# CDH-v4_1.net
KiCad netlist of a schematic drawn in EAGLE
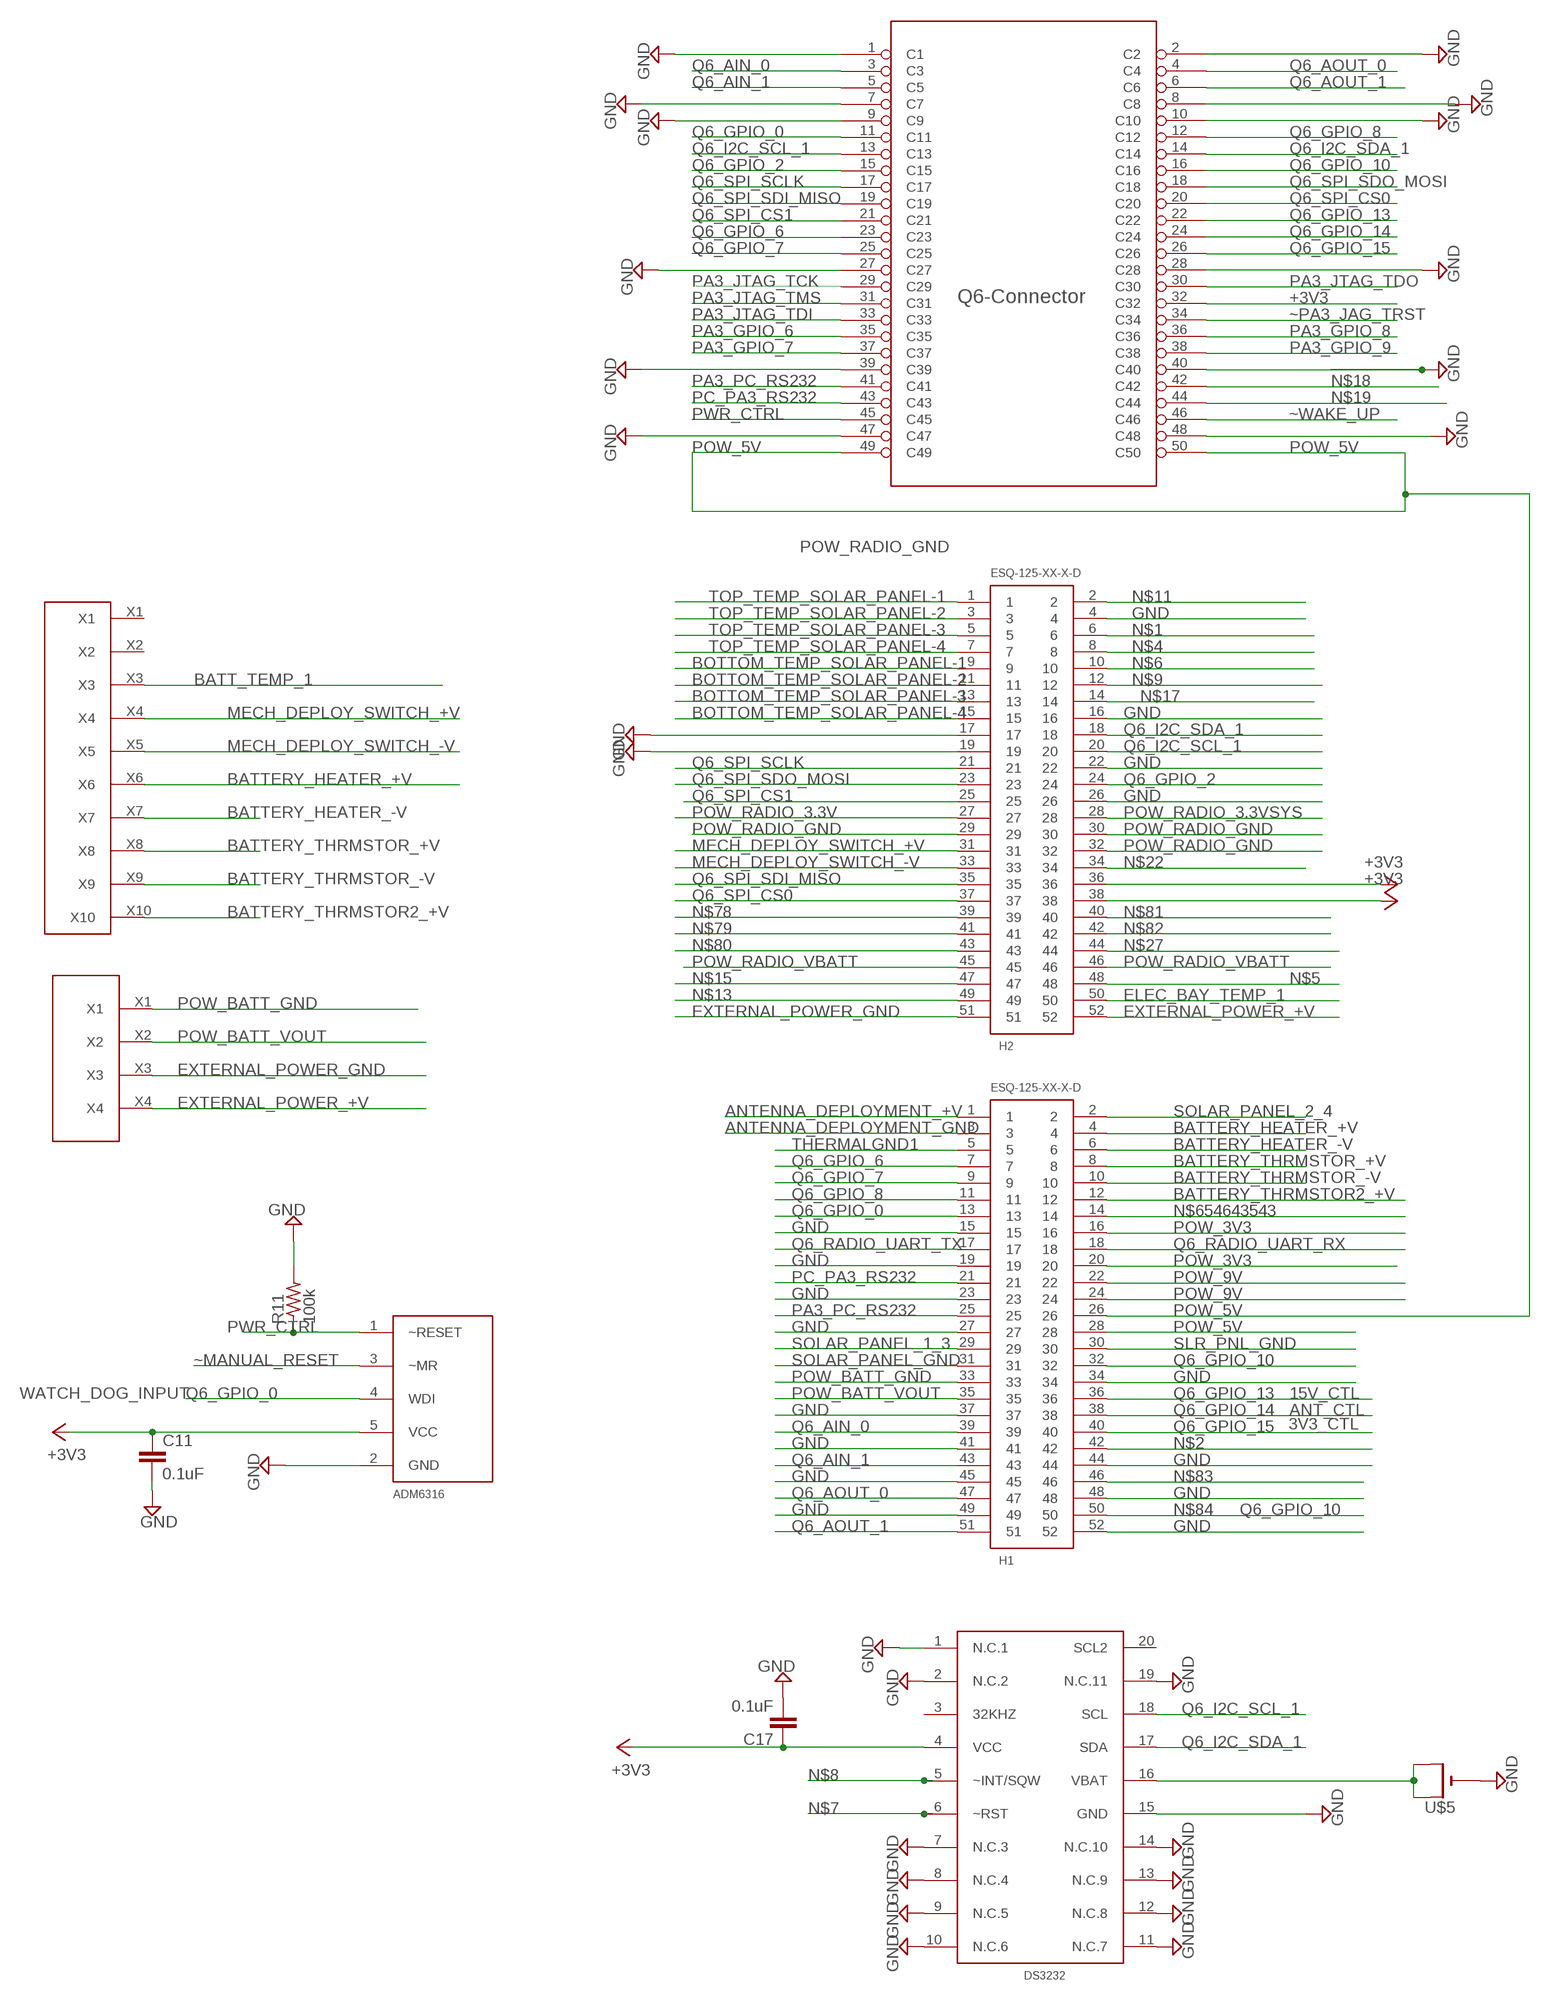
[diagram p0: schematic, sheet 1, part 1 of 2]
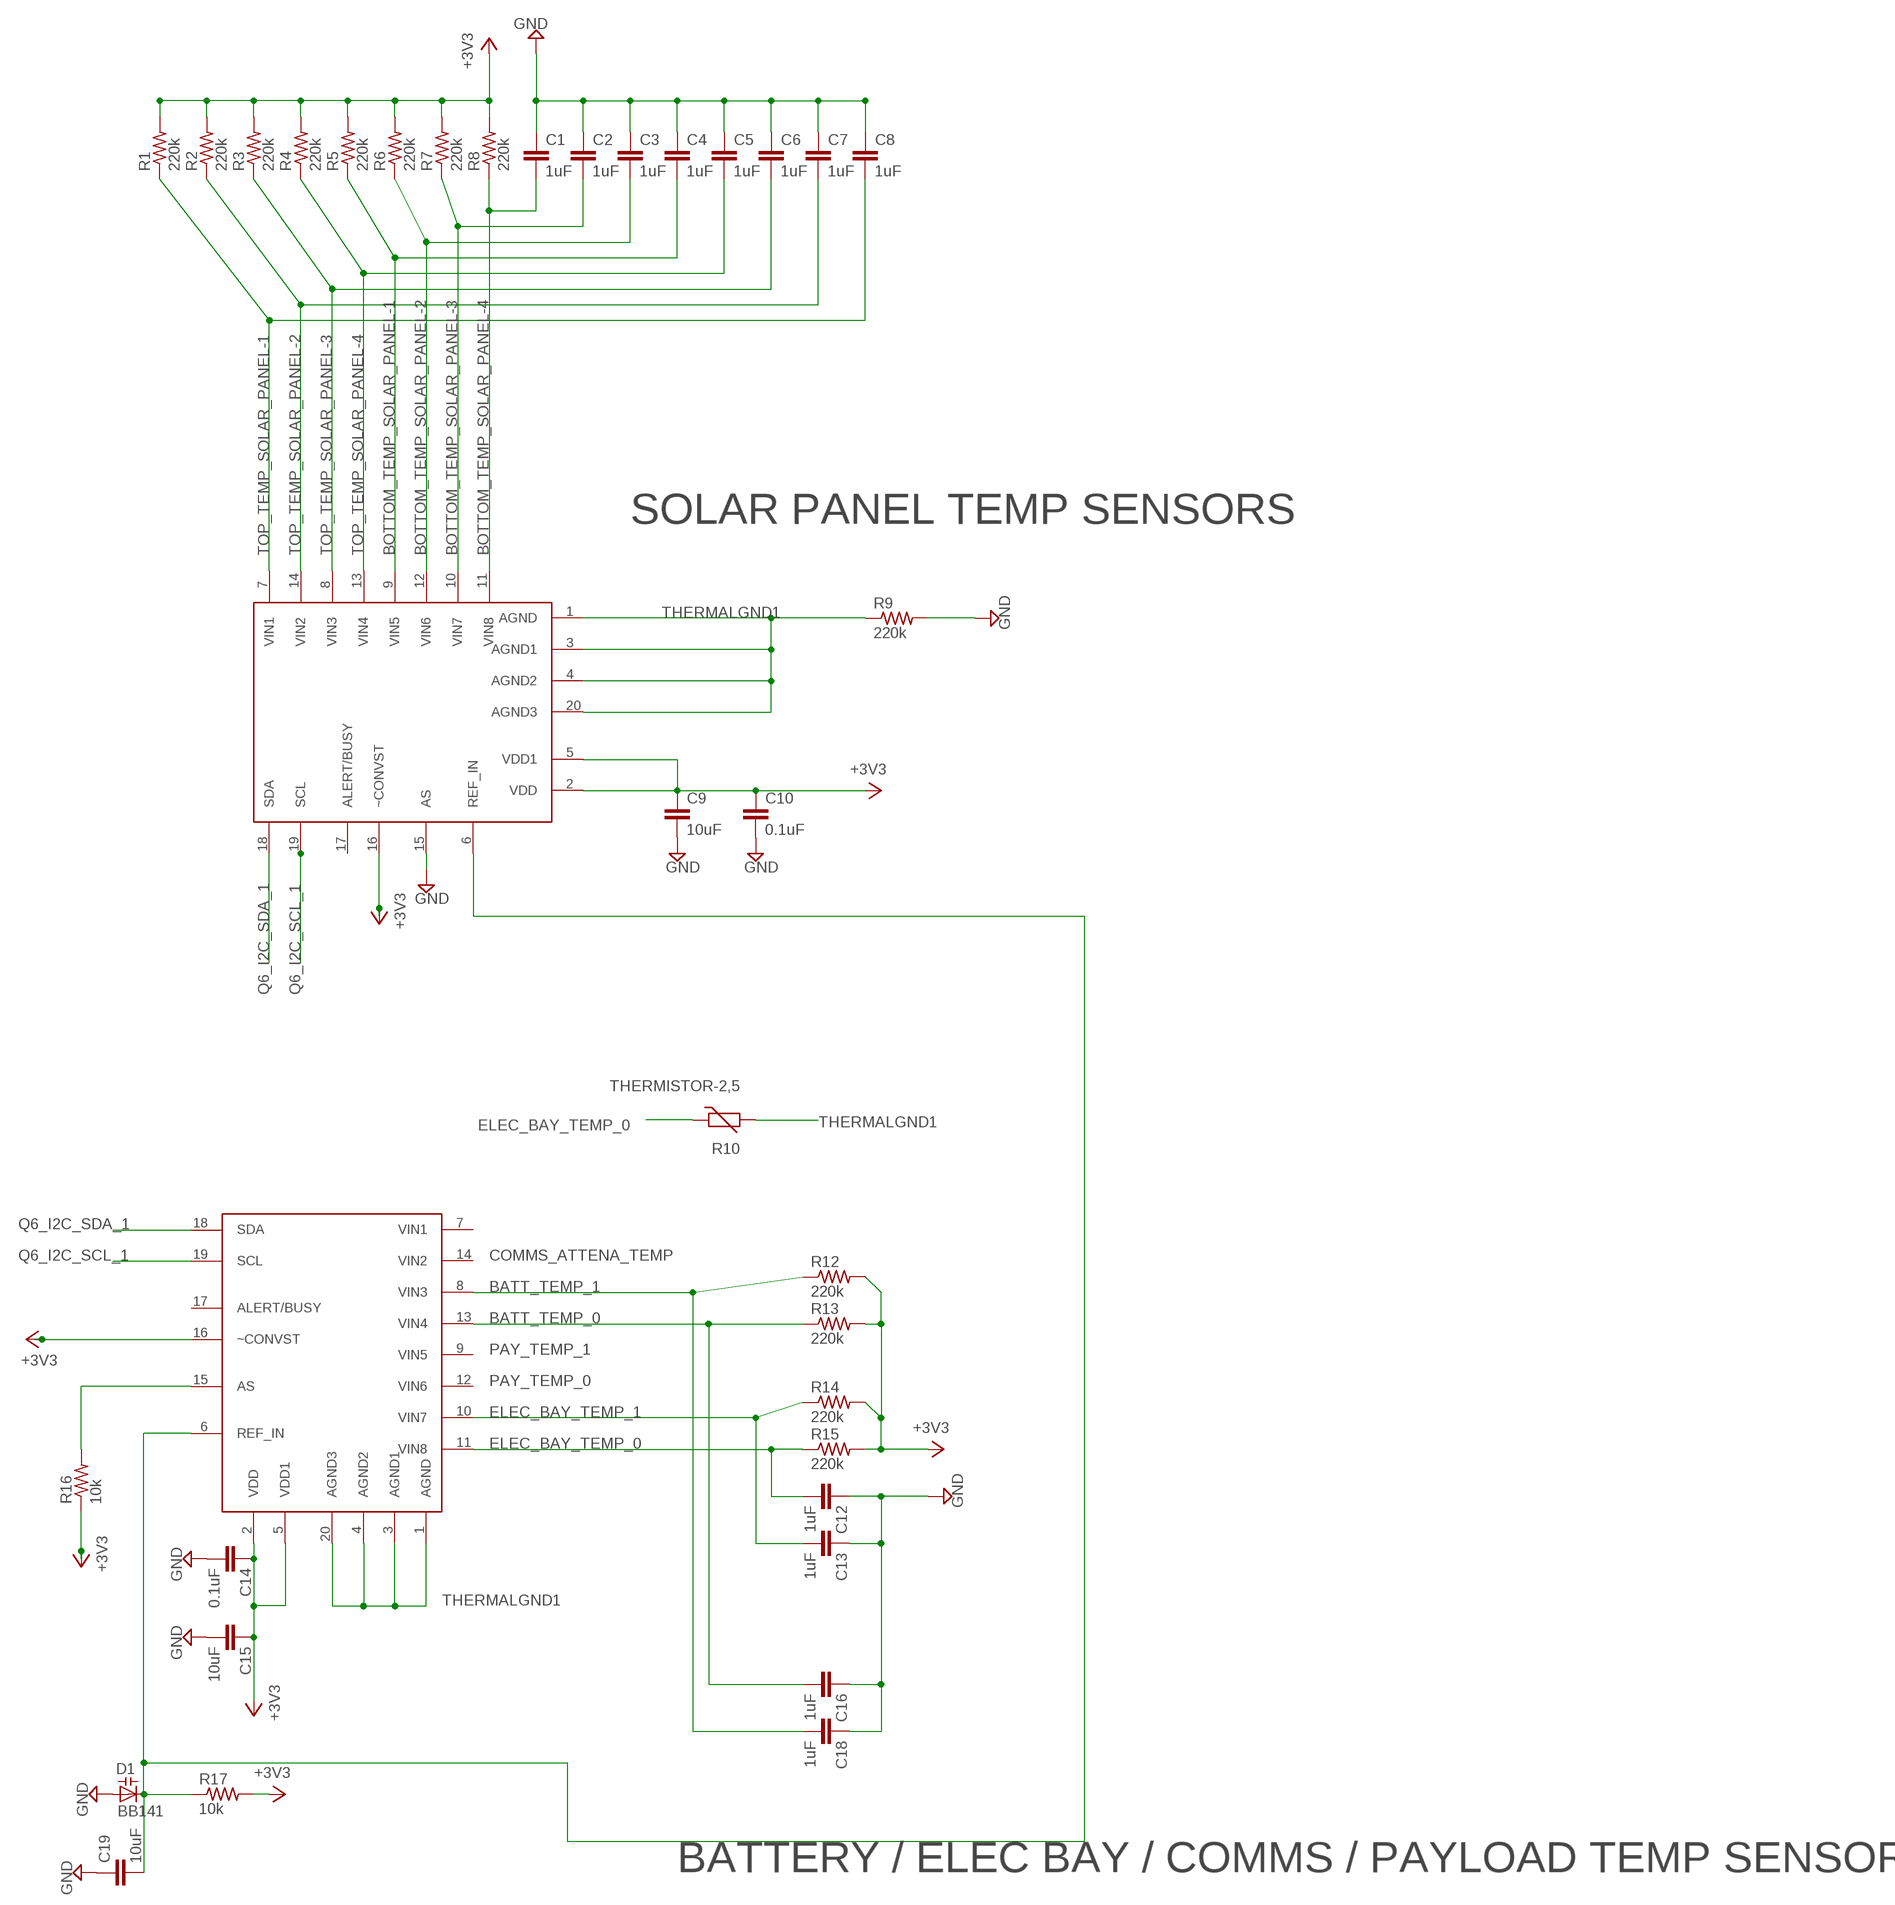
[diagram p1: schematic, sheet 1, part 2 of 2]

(export (version "E")
  (design (tool "Eeschema 10.0.6"))
  (components
    (comp (ref "ADC_TEMP_1")
      (value "AD7998-1")
      (footprint "eagle-import:TSSOP20")
      (libsource (lib "eagle-import") (part "AD7998-1"))
    )
    (comp (ref "ADC_TEMP_2")
      (value "AD7998-1")
      (footprint "eagle-import:TSSOP20")
      (libsource (lib "eagle-import") (part "AD7998-1"))
    )
    (comp (ref "C1")
      (value "1uF")
      (footprint "eagle-import:C2012")
      (libsource (lib "eagle-import") (part "C-EUC2012"))
    )
    (comp (ref "C2")
      (value "1uF")
      (footprint "eagle-import:C2012")
      (libsource (lib "eagle-import") (part "C-EUC2012"))
    )
    (comp (ref "C3")
      (value "1uF")
      (footprint "eagle-import:C2012")
      (libsource (lib "eagle-import") (part "C-EUC2012"))
    )
    (comp (ref "C4")
      (value "1uF")
      (footprint "eagle-import:C2012")
      (libsource (lib "eagle-import") (part "C-EUC2012"))
    )
    (comp (ref "C5")
      (value "1uF")
      (footprint "eagle-import:C2012")
      (libsource (lib "eagle-import") (part "C-EUC2012"))
    )
    (comp (ref "C6")
      (value "1uF")
      (footprint "eagle-import:C2012")
      (libsource (lib "eagle-import") (part "C-EUC2012"))
    )
    (comp (ref "C7")
      (value "1uF")
      (footprint "eagle-import:C2012")
      (libsource (lib "eagle-import") (part "C-EUC2012"))
    )
    (comp (ref "C8")
      (value "1uF")
      (footprint "eagle-import:C2012")
      (libsource (lib "eagle-import") (part "C-EUC2012"))
    )
    (comp (ref "C9")
      (value "10uF")
      (footprint "eagle-import:C2012")
      (libsource (lib "eagle-import") (part "C-EUC2012"))
    )
    (comp (ref "C10")
      (value "0.1uF")
      (footprint "eagle-import:C2012")
      (libsource (lib "eagle-import") (part "C-EUC2012"))
    )
    (comp (ref "C11")
      (value "0.1uF")
      (footprint "eagle-import:C2012")
      (libsource (lib "eagle-import") (part "C-EUC2012"))
    )
    (comp (ref "C12")
      (value "1uF")
      (footprint "eagle-import:C2012")
      (libsource (lib "eagle-import") (part "C-EUC2012"))
    )
    (comp (ref "C13")
      (value "1uF")
      (footprint "eagle-import:C2012")
      (libsource (lib "eagle-import") (part "C-EUC2012"))
    )
    (comp (ref "C14")
      (value "0.1uF")
      (footprint "eagle-import:C2012")
      (libsource (lib "eagle-import") (part "C-EUC2012"))
    )
    (comp (ref "C15")
      (value "10uF")
      (footprint "eagle-import:C2012")
      (libsource (lib "eagle-import") (part "C-EUC2012"))
    )
    (comp (ref "C16")
      (value "1uF")
      (footprint "eagle-import:C2012")
      (libsource (lib "eagle-import") (part "C-EUC2012"))
    )
    (comp (ref "C17")
      (value "0.1uF")
      (footprint "eagle-import:C2012")
      (libsource (lib "eagle-import") (part "C-EUC2012"))
    )
    (comp (ref "C18")
      (value "1uF")
      (footprint "eagle-import:C2012")
      (libsource (lib "eagle-import") (part "C-EUC2012"))
    )
    (comp (ref "C19")
      (value "10uF")
      (footprint "eagle-import:C2012")
      (libsource (lib "eagle-import") (part "C-EUC2012"))
    )
    (comp (ref "D1")
      (value "BB141")
      (footprint "eagle-import:SOD523")
      (libsource (lib "eagle-import") (part "BB141"))
    )
    (comp (ref "H1")
      (value "ESQ-125-XX-X-D")
      (footprint "eagle-import:ESQ-125-XX-X-D")
      (libsource (lib "eagle-import") (part "ESQ-125-XX-X-D"))
    )
    (comp (ref "H2")
      (value "ESQ-125-XX-X-D")
      (footprint "eagle-import:ESQ-125-XX-X-D")
      (libsource (lib "eagle-import") (part "ESQ-125-XX-X-D"))
    )
    (comp (ref "R1")
      (value "220k")
      (footprint "eagle-import:R2012")
      (libsource (lib "eagle-import") (part "R-US_R2012"))
    )
    (comp (ref "R2")
      (value "220k")
      (footprint "eagle-import:R2012")
      (libsource (lib "eagle-import") (part "R-US_R2012"))
    )
    (comp (ref "R3")
      (value "220k")
      (footprint "eagle-import:R2012")
      (libsource (lib "eagle-import") (part "R-US_R2012"))
    )
    (comp (ref "R4")
      (value "220k")
      (footprint "eagle-import:R2012")
      (libsource (lib "eagle-import") (part "R-US_R2012"))
    )
    (comp (ref "R5")
      (value "220k")
      (footprint "eagle-import:R2012")
      (libsource (lib "eagle-import") (part "R-US_R2012"))
    )
    (comp (ref "R6")
      (value "220k")
      (footprint "eagle-import:R2012")
      (libsource (lib "eagle-import") (part "R-US_R2012"))
    )
    (comp (ref "R7")
      (value "220k")
      (footprint "eagle-import:R2012")
      (libsource (lib "eagle-import") (part "R-US_R2012"))
    )
    (comp (ref "R8")
      (value "220k")
      (footprint "eagle-import:R2012")
      (libsource (lib "eagle-import") (part "R-US_R2012"))
    )
    (comp (ref "R9")
      (value "220k")
      (footprint "eagle-import:R2012")
      (libsource (lib "eagle-import") (part "R-US_R2012"))
    )
    (comp (ref "R10")
      (value "THERMISTOR-2,5")
      (footprint "eagle-import:RS-2,5")
      (libsource (lib "eagle-import") (part "THERMISTOR-2,5"))
    )
    (comp (ref "R11")
      (value "100k")
      (footprint "eagle-import:R2012")
      (libsource (lib "eagle-import") (part "R-US_R2012"))
    )
    (comp (ref "R12")
      (value "220k")
      (footprint "eagle-import:R2012")
      (libsource (lib "eagle-import") (part "R-US_R2012"))
    )
    (comp (ref "R13")
      (value "220k")
      (footprint "eagle-import:R2012")
      (libsource (lib "eagle-import") (part "R-US_R2012"))
    )
    (comp (ref "R14")
      (value "220k")
      (footprint "eagle-import:R2012")
      (libsource (lib "eagle-import") (part "R-US_R2012"))
    )
    (comp (ref "R15")
      (value "220k")
      (footprint "eagle-import:R2012")
      (libsource (lib "eagle-import") (part "R-US_R2012"))
    )
    (comp (ref "R16")
      (value "10k")
      (footprint "eagle-import:R2012")
      (libsource (lib "eagle-import") (part "R-US_R2012"))
    )
    (comp (ref "R17")
      (value "10k")
      (footprint "eagle-import:R2012")
      (libsource (lib "eagle-import") (part "R-US_R2012"))
    )
    (comp (ref "U$1")
      (value "SMFC")
      (footprint "eagle-import:SFMC-107-01-XX-D")
      (libsource (lib "eagle-import") (part "SMFC"))
    )
    (comp (ref "U$2")
      (value "M80-5000000M1-10-331-000")
      (footprint "eagle-import:M80-5000000M1")
      (libsource (lib "eagle-import") (part "M80-5000000M1-10-331-000"))
    )
    (comp (ref "U$3")
      (value "M80-5000000M1-10-331-00-000")
      (footprint "eagle-import:M80-5000000M1-04-331-00-000")
      (libsource (lib "eagle-import") (part "M80-5000000M1-10-331-00-000"))
    )
    (comp (ref "U$4")
      (value "ADM6316/ADM6320")
      (footprint "eagle-import:SOT23-5")
      (libsource (lib "eagle-import") (part "ADM6316/ADM6320"))
    )
    (comp (ref "U$5")
      (value "CR1220SMT")
      (footprint "eagle-import:CR1220-SMD")
      (libsource (lib "eagle-import") (part "CR1220SMT"))
    )
    (comp (ref "U$6")
      (value "DS3232")
      (footprint "eagle-import:SO20L")
      (libsource (lib "eagle-import") (part "DS3232"))
    )
  )
  (nets
    (net (code "1") (name "+3V3") (class "Default")
      (node (ref "ADC_TEMP_1") (pin "16") (pinfunction "~{CONVST}_16") (pintype "bidirectional"))
      (node (ref "ADC_TEMP_1") (pin "2") (pinfunction "VDD_2") (pintype "bidirectional"))
      (node (ref "ADC_TEMP_1") (pin "5") (pinfunction "VDD1_5") (pintype "bidirectional"))
      (node (ref "ADC_TEMP_2") (pin "16") (pinfunction "~{CONVST}_16") (pintype "bidirectional"))
      (node (ref "ADC_TEMP_2") (pin "2") (pinfunction "VDD_2") (pintype "bidirectional"))
      (node (ref "ADC_TEMP_2") (pin "5") (pinfunction "VDD1_5") (pintype "bidirectional"))
      (node (ref "C10") (pin "1") (pinfunction "1_1") (pintype "passive"))
      (node (ref "C11") (pin "1") (pinfunction "1_1") (pintype "passive"))
      (node (ref "C14") (pin "1") (pinfunction "1_1") (pintype "passive"))
      (node (ref "C15") (pin "1") (pinfunction "1_1") (pintype "passive"))
      (node (ref "C17") (pin "1") (pinfunction "1_1") (pintype "passive"))
      (node (ref "C9") (pin "1") (pinfunction "1_1") (pintype "passive"))
      (node (ref "H2") (pin "36") (pinfunction "36_36") (pintype "bidirectional"))
      (node (ref "H2") (pin "38") (pinfunction "38_38") (pintype "bidirectional"))
      (node (ref "R1") (pin "2") (pinfunction "2_2") (pintype "passive"))
      (node (ref "R12") (pin "2") (pinfunction "2_2") (pintype "passive"))
      (node (ref "R13") (pin "2") (pinfunction "2_2") (pintype "passive"))
      (node (ref "R14") (pin "2") (pinfunction "2_2") (pintype "passive"))
      (node (ref "R15") (pin "2") (pinfunction "2_2") (pintype "passive"))
      (node (ref "R16") (pin "1") (pinfunction "1_1") (pintype "passive"))
      (node (ref "R17") (pin "2") (pinfunction "2_2") (pintype "passive"))
      (node (ref "R2") (pin "2") (pinfunction "2_2") (pintype "passive"))
      (node (ref "R3") (pin "2") (pinfunction "2_2") (pintype "passive"))
      (node (ref "R4") (pin "2") (pinfunction "2_2") (pintype "passive"))
      (node (ref "R5") (pin "2") (pinfunction "2_2") (pintype "passive"))
      (node (ref "R6") (pin "2") (pinfunction "2_2") (pintype "passive"))
      (node (ref "R7") (pin "2") (pinfunction "2_2") (pintype "passive"))
      (node (ref "R8") (pin "2") (pinfunction "2_2") (pintype "passive"))
      (node (ref "U$1") (pin "32") (pinfunction "C32_32") (pintype "bidirectional"))
      (node (ref "U$4") (pin "5") (pinfunction "VCC_5") (pintype "bidirectional"))
      (node (ref "U$6") (pin "4") (pinfunction "VCC_4") (pintype "bidirectional"))
    )
    (net (code "2") (name "/ANTENNA_DEPLOYMENT_+V") (class "Default")
      (node (ref "H1") (pin "1") (pinfunction "1_1") (pintype "bidirectional"))
    )
    (net (code "3") (name "/ANTENNA_DEPLOYMENT_GND") (class "Default")
      (node (ref "H1") (pin "3") (pinfunction "3_3") (pintype "bidirectional"))
    )
    (net (code "4") (name "/BATTERY_HEATER_+V") (class "Default")
      (node (ref "H1") (pin "4") (pinfunction "4_4") (pintype "bidirectional"))
      (node (ref "U$2") (pin "X6") (pinfunction "X6_X6") (pintype "bidirectional"))
    )
    (net (code "5") (name "/BATTERY_HEATER_-V") (class "Default")
      (node (ref "H1") (pin "6") (pinfunction "6_6") (pintype "bidirectional"))
      (node (ref "U$2") (pin "X7") (pinfunction "X7_X7") (pintype "bidirectional"))
    )
    (net (code "6") (name "/BATTERY_THRMSTOR2_+V") (class "Default")
      (node (ref "H1") (pin "12") (pinfunction "12_12") (pintype "bidirectional"))
      (node (ref "U$2") (pin "X10") (pinfunction "X10_X10") (pintype "bidirectional"))
    )
    (net (code "7") (name "/BATTERY_THRMSTOR_+V") (class "Default")
      (node (ref "H1") (pin "8") (pinfunction "8_8") (pintype "bidirectional"))
      (node (ref "U$2") (pin "X8") (pinfunction "X8_X8") (pintype "bidirectional"))
    )
    (net (code "8") (name "/BATTERY_THRMSTOR_-V") (class "Default")
      (node (ref "H1") (pin "10") (pinfunction "10_10") (pintype "bidirectional"))
      (node (ref "U$2") (pin "X9") (pinfunction "X9_X9") (pintype "bidirectional"))
    )
    (net (code "9") (name "/BATT_TEMP_1") (class "Default")
      (node (ref "ADC_TEMP_2") (pin "8") (pinfunction "VIN3_8") (pintype "bidirectional"))
      (node (ref "C18") (pin "2") (pinfunction "2_2") (pintype "passive"))
      (node (ref "R12") (pin "1") (pinfunction "1_1") (pintype "passive"))
      (node (ref "U$2") (pin "X3") (pinfunction "X3_X3") (pintype "bidirectional"))
    )
    (net (code "10") (name "/BOTTOM_TEMP_SOLAR_PANEL-1") (class "Default")
      (node (ref "ADC_TEMP_1") (pin "9") (pinfunction "VIN5_9") (pintype "bidirectional"))
      (node (ref "C4") (pin "2") (pinfunction "2_2") (pintype "passive"))
      (node (ref "H2") (pin "9") (pinfunction "9_9") (pintype "bidirectional"))
      (node (ref "R5") (pin "1") (pinfunction "1_1") (pintype "passive"))
    )
    (net (code "11") (name "/BOTTOM_TEMP_SOLAR_PANEL-2") (class "Default")
      (node (ref "ADC_TEMP_1") (pin "12") (pinfunction "VIN6_12") (pintype "bidirectional"))
      (node (ref "C3") (pin "2") (pinfunction "2_2") (pintype "passive"))
      (node (ref "H2") (pin "11") (pinfunction "11_11") (pintype "bidirectional"))
      (node (ref "R6") (pin "1") (pinfunction "1_1") (pintype "passive"))
    )
    (net (code "12") (name "/BOTTOM_TEMP_SOLAR_PANEL-3") (class "Default")
      (node (ref "ADC_TEMP_1") (pin "10") (pinfunction "VIN7_10") (pintype "bidirectional"))
      (node (ref "C2") (pin "2") (pinfunction "2_2") (pintype "passive"))
      (node (ref "H2") (pin "13") (pinfunction "13_13") (pintype "bidirectional"))
      (node (ref "R7") (pin "1") (pinfunction "1_1") (pintype "passive"))
    )
    (net (code "13") (name "/BOTTOM_TEMP_SOLAR_PANEL-4") (class "Default")
      (node (ref "ADC_TEMP_1") (pin "11") (pinfunction "VIN8_11") (pintype "bidirectional"))
      (node (ref "C1") (pin "2") (pinfunction "2_2") (pintype "passive"))
      (node (ref "H2") (pin "15") (pinfunction "15_15") (pintype "bidirectional"))
      (node (ref "R8") (pin "1") (pinfunction "1_1") (pintype "passive"))
    )
    (net (code "14") (name "/ELEC_BAY_TEMP_0") (class "Default")
      (node (ref "ADC_TEMP_2") (pin "11") (pinfunction "VIN8_11") (pintype "bidirectional"))
      (node (ref "C12") (pin "2") (pinfunction "2_2") (pintype "passive"))
      (node (ref "R10") (pin "1") (pinfunction "1_1") (pintype "passive"))
      (node (ref "R15") (pin "1") (pinfunction "1_1") (pintype "passive"))
    )
    (net (code "15") (name "/ELEC_BAY_TEMP_1") (class "Default")
      (node (ref "ADC_TEMP_2") (pin "10") (pinfunction "VIN7_10") (pintype "bidirectional"))
      (node (ref "C13") (pin "2") (pinfunction "2_2") (pintype "passive"))
      (node (ref "H2") (pin "50") (pinfunction "50_50") (pintype "bidirectional"))
      (node (ref "R14") (pin "1") (pinfunction "1_1") (pintype "passive"))
    )
    (net (code "16") (name "/EXTERNAL_POWER_+V") (class "Default")
      (node (ref "H2") (pin "52") (pinfunction "52_52") (pintype "bidirectional"))
      (node (ref "U$3") (pin "X4") (pinfunction "X4_X4") (pintype "bidirectional"))
    )
    (net (code "17") (name "/EXTERNAL_POWER_GND") (class "Default")
      (node (ref "H2") (pin "51") (pinfunction "51_51") (pintype "bidirectional"))
      (node (ref "U$3") (pin "X3") (pinfunction "X3_X3") (pintype "bidirectional"))
    )
    (net (code "18") (name "/MECH_DEPLOY_SWITCH_+V") (class "Default")
      (node (ref "H2") (pin "31") (pinfunction "31_31") (pintype "bidirectional"))
      (node (ref "U$2") (pin "X4") (pinfunction "X4_X4") (pintype "bidirectional"))
    )
    (net (code "19") (name "/MECH_DEPLOY_SWITCH_-V") (class "Default")
      (node (ref "H2") (pin "33") (pinfunction "33_33") (pintype "bidirectional"))
      (node (ref "U$2") (pin "X5") (pinfunction "X5_X5") (pintype "bidirectional"))
    )
    (net (code "20") (name "/N$1") (class "Default")
      (node (ref "H2") (pin "6") (pinfunction "6_6") (pintype "bidirectional"))
    )
    (net (code "21") (name "/N$2") (class "Default")
      (node (ref "H1") (pin "42") (pinfunction "42_42") (pintype "bidirectional"))
    )
    (net (code "22") (name "/N$4") (class "Default")
      (node (ref "H2") (pin "8") (pinfunction "8_8") (pintype "bidirectional"))
    )
    (net (code "23") (name "/N$5") (class "Default")
      (node (ref "H2") (pin "48") (pinfunction "48_48") (pintype "bidirectional"))
    )
    (net (code "24") (name "/N$6") (class "Default")
      (node (ref "H2") (pin "10") (pinfunction "10_10") (pintype "bidirectional"))
    )
    (net (code "25") (name "/N$7") (class "Default")
      (node (ref "U$6") (pin "6") (pinfunction "~{RST}_6") (pintype "bidirectional"))
    )
    (net (code "26") (name "/N$8") (class "Default")
      (node (ref "U$6") (pin "5") (pinfunction "~{INT/SQW}_5") (pintype "bidirectional"))
    )
    (net (code "27") (name "/N$9") (class "Default")
      (node (ref "H2") (pin "12") (pinfunction "12_12") (pintype "bidirectional"))
    )
    (net (code "28") (name "/N$11") (class "Default")
      (node (ref "H2") (pin "2") (pinfunction "2_2") (pintype "bidirectional"))
    )
    (net (code "29") (name "/N$13") (class "Default")
      (node (ref "H2") (pin "49") (pinfunction "49_49") (pintype "bidirectional"))
    )
    (net (code "30") (name "/N$15") (class "Default")
      (node (ref "H2") (pin "47") (pinfunction "47_47") (pintype "bidirectional"))
    )
    (net (code "31") (name "/N$17") (class "Default")
      (node (ref "H2") (pin "14") (pinfunction "14_14") (pintype "bidirectional"))
    )
    (net (code "32") (name "/N$18") (class "Default")
      (node (ref "U$1") (pin "42") (pinfunction "C42_42") (pintype "bidirectional"))
    )
    (net (code "33") (name "/N$19") (class "Default")
      (node (ref "U$1") (pin "44") (pinfunction "C44_44") (pintype "bidirectional"))
    )
    (net (code "34") (name "/N$22") (class "Default")
      (node (ref "H2") (pin "34") (pinfunction "34_34") (pintype "bidirectional"))
    )
    (net (code "35") (name "/N$27") (class "Default")
      (node (ref "H2") (pin "44") (pinfunction "44_44") (pintype "bidirectional"))
    )
    (net (code "36") (name "/N$78") (class "Default")
      (node (ref "H2") (pin "39") (pinfunction "39_39") (pintype "bidirectional"))
    )
    (net (code "37") (name "/N$79") (class "Default")
      (node (ref "H2") (pin "41") (pinfunction "41_41") (pintype "bidirectional"))
    )
    (net (code "38") (name "/N$80") (class "Default")
      (node (ref "H2") (pin "43") (pinfunction "43_43") (pintype "bidirectional"))
    )
    (net (code "39") (name "/N$81") (class "Default")
      (node (ref "H2") (pin "40") (pinfunction "40_40") (pintype "bidirectional"))
    )
    (net (code "40") (name "/N$82") (class "Default")
      (node (ref "H2") (pin "42") (pinfunction "42_42") (pintype "bidirectional"))
    )
    (net (code "41") (name "/N$83") (class "Default")
      (node (ref "H1") (pin "46") (pinfunction "46_46") (pintype "bidirectional"))
    )
    (net (code "42") (name "/N$84") (class "Default")
      (node (ref "H1") (pin "50") (pinfunction "50_50") (pintype "bidirectional"))
    )
    (net (code "43") (name "/N$654643543") (class "Default")
      (node (ref "H1") (pin "14") (pinfunction "14_14") (pintype "bidirectional"))
    )
    (net (code "44") (name "/PA3_GPIO_6") (class "Default")
      (node (ref "U$1") (pin "35") (pinfunction "C35_35") (pintype "bidirectional"))
    )
    (net (code "45") (name "/PA3_GPIO_7") (class "Default")
      (node (ref "U$1") (pin "37") (pinfunction "C37_37") (pintype "bidirectional"))
    )
    (net (code "46") (name "/PA3_GPIO_8") (class "Default")
      (node (ref "U$1") (pin "36") (pinfunction "C36_36") (pintype "bidirectional"))
    )
    (net (code "47") (name "/PA3_GPIO_9") (class "Default")
      (node (ref "U$1") (pin "38") (pinfunction "C38_38") (pintype "bidirectional"))
    )
    (net (code "48") (name "/PA3_JTAG_TCK") (class "Default")
      (node (ref "U$1") (pin "29") (pinfunction "C29_29") (pintype "bidirectional"))
    )
    (net (code "49") (name "/PA3_JTAG_TDI") (class "Default")
      (node (ref "U$1") (pin "33") (pinfunction "C33_33") (pintype "bidirectional"))
    )
    (net (code "50") (name "/PA3_JTAG_TDO") (class "Default")
      (node (ref "U$1") (pin "30") (pinfunction "C30_30") (pintype "bidirectional"))
    )
    (net (code "51") (name "/PA3_JTAG_TMS") (class "Default")
      (node (ref "U$1") (pin "31") (pinfunction "C31_31") (pintype "bidirectional"))
    )
    (net (code "52") (name "/PA3_PC_RS232") (class "Default")
      (node (ref "H1") (pin "25") (pinfunction "25_25") (pintype "bidirectional"))
      (node (ref "U$1") (pin "41") (pinfunction "C41_41") (pintype "bidirectional"))
    )
    (net (code "53") (name "/PC_PA3_RS232") (class "Default")
      (node (ref "H1") (pin "21") (pinfunction "21_21") (pintype "bidirectional"))
      (node (ref "U$1") (pin "43") (pinfunction "C43_43") (pintype "bidirectional"))
    )
    (net (code "54") (name "/POW_3V3") (class "Default")
      (node (ref "H1") (pin "16") (pinfunction "16_16") (pintype "bidirectional"))
      (node (ref "H1") (pin "20") (pinfunction "20_20") (pintype "bidirectional"))
    )
    (net (code "55") (name "/POW_5V") (class "Default")
      (node (ref "H1") (pin "26") (pinfunction "26_26") (pintype "bidirectional"))
      (node (ref "H1") (pin "28") (pinfunction "28_28") (pintype "bidirectional"))
      (node (ref "U$1") (pin "49") (pinfunction "C49_49") (pintype "bidirectional"))
      (node (ref "U$1") (pin "50") (pinfunction "C50_50") (pintype "bidirectional"))
    )
    (net (code "56") (name "/POW_9V") (class "Default")
      (node (ref "H1") (pin "22") (pinfunction "22_22") (pintype "bidirectional"))
      (node (ref "H1") (pin "24") (pinfunction "24_24") (pintype "bidirectional"))
    )
    (net (code "57") (name "/POW_BATT_GND") (class "Default")
      (node (ref "H1") (pin "33") (pinfunction "33_33") (pintype "bidirectional"))
      (node (ref "U$3") (pin "X1") (pinfunction "X1_X1") (pintype "bidirectional"))
    )
    (net (code "58") (name "/POW_BATT_VOUT") (class "Default")
      (node (ref "H1") (pin "35") (pinfunction "35_35") (pintype "bidirectional"))
      (node (ref "U$3") (pin "X2") (pinfunction "X2_X2") (pintype "bidirectional"))
    )
    (net (code "59") (name "/POW_RADIO_3.3V") (class "Default")
      (node (ref "H2") (pin "27") (pinfunction "27_27") (pintype "bidirectional"))
    )
    (net (code "60") (name "/POW_RADIO_3.3VSYS") (class "Default")
      (node (ref "H2") (pin "28") (pinfunction "28_28") (pintype "bidirectional"))
    )
    (net (code "61") (name "/POW_RADIO_GND") (class "Default")
      (node (ref "H2") (pin "29") (pinfunction "29_29") (pintype "bidirectional"))
      (node (ref "H2") (pin "30") (pinfunction "30_30") (pintype "bidirectional"))
      (node (ref "H2") (pin "32") (pinfunction "32_32") (pintype "bidirectional"))
    )
    (net (code "62") (name "/POW_RADIO_VBATT") (class "Default")
      (node (ref "H2") (pin "45") (pinfunction "45_45") (pintype "bidirectional"))
      (node (ref "H2") (pin "46") (pinfunction "46_46") (pintype "bidirectional"))
    )
    (net (code "63") (name "/PWR_CTRL") (class "Default")
      (node (ref "R11") (pin "1") (pinfunction "1_1") (pintype "passive"))
      (node (ref "U$1") (pin "45") (pinfunction "C45_45") (pintype "bidirectional"))
      (node (ref "U$4") (pin "1") (pinfunction "~{RESET}_1") (pintype "bidirectional"))
    )
    (net (code "64") (name "/Q6_AIN_0") (class "Default")
      (node (ref "H1") (pin "39") (pinfunction "39_39") (pintype "bidirectional"))
      (node (ref "U$1") (pin "3") (pinfunction "C3_3") (pintype "bidirectional"))
    )
    (net (code "65") (name "/Q6_AIN_1") (class "Default")
      (node (ref "H1") (pin "43") (pinfunction "43_43") (pintype "bidirectional"))
      (node (ref "U$1") (pin "5") (pinfunction "C5_5") (pintype "bidirectional"))
    )
    (net (code "66") (name "/Q6_AOUT_0") (class "Default")
      (node (ref "H1") (pin "47") (pinfunction "47_47") (pintype "bidirectional"))
      (node (ref "U$1") (pin "4") (pinfunction "C4_4") (pintype "bidirectional"))
    )
    (net (code "67") (name "/Q6_AOUT_1") (class "Default")
      (node (ref "H1") (pin "51") (pinfunction "51_51") (pintype "bidirectional"))
      (node (ref "U$1") (pin "6") (pinfunction "C6_6") (pintype "bidirectional"))
    )
    (net (code "68") (name "/Q6_GPIO_0") (class "Default")
      (node (ref "H1") (pin "13") (pinfunction "13_13") (pintype "bidirectional"))
      (node (ref "U$1") (pin "11") (pinfunction "C11_11") (pintype "bidirectional"))
      (node (ref "U$4") (pin "4") (pinfunction "WDI_4") (pintype "bidirectional"))
    )
    (net (code "69") (name "/Q6_GPIO_2") (class "Default")
      (node (ref "H2") (pin "24") (pinfunction "24_24") (pintype "bidirectional"))
      (node (ref "U$1") (pin "15") (pinfunction "C15_15") (pintype "bidirectional"))
    )
    (net (code "70") (name "/Q6_GPIO_6") (class "Default")
      (node (ref "H1") (pin "7") (pinfunction "7_7") (pintype "bidirectional"))
      (node (ref "U$1") (pin "23") (pinfunction "C23_23") (pintype "bidirectional"))
    )
    (net (code "71") (name "/Q6_GPIO_7") (class "Default")
      (node (ref "H1") (pin "9") (pinfunction "9_9") (pintype "bidirectional"))
      (node (ref "U$1") (pin "25") (pinfunction "C25_25") (pintype "bidirectional"))
    )
    (net (code "72") (name "/Q6_GPIO_8") (class "Default")
      (node (ref "H1") (pin "11") (pinfunction "11_11") (pintype "bidirectional"))
      (node (ref "U$1") (pin "12") (pinfunction "C12_12") (pintype "bidirectional"))
    )
    (net (code "73") (name "/Q6_GPIO_10") (class "Default")
      (node (ref "H1") (pin "32") (pinfunction "32_32") (pintype "bidirectional"))
      (node (ref "U$1") (pin "16") (pinfunction "C16_16") (pintype "bidirectional"))
    )
    (net (code "74") (name "/Q6_GPIO_13") (class "Default")
      (node (ref "H1") (pin "36") (pinfunction "36_36") (pintype "bidirectional"))
      (node (ref "U$1") (pin "22") (pinfunction "C22_22") (pintype "bidirectional"))
    )
    (net (code "75") (name "/Q6_GPIO_14") (class "Default")
      (node (ref "H1") (pin "38") (pinfunction "38_38") (pintype "bidirectional"))
      (node (ref "U$1") (pin "24") (pinfunction "C24_24") (pintype "bidirectional"))
    )
    (net (code "76") (name "/Q6_GPIO_15") (class "Default")
      (node (ref "H1") (pin "40") (pinfunction "40_40") (pintype "bidirectional"))
      (node (ref "U$1") (pin "26") (pinfunction "C26_26") (pintype "bidirectional"))
    )
    (net (code "77") (name "/Q6_I2C_SCL_1") (class "Default")
      (node (ref "ADC_TEMP_1") (pin "19") (pinfunction "SCL_19") (pintype "bidirectional"))
      (node (ref "ADC_TEMP_2") (pin "19") (pinfunction "SCL_19") (pintype "bidirectional"))
      (node (ref "H2") (pin "20") (pinfunction "20_20") (pintype "bidirectional"))
      (node (ref "U$1") (pin "13") (pinfunction "C13_13") (pintype "bidirectional"))
      (node (ref "U$6") (pin "18") (pinfunction "SCL_18") (pintype "bidirectional"))
    )
    (net (code "78") (name "/Q6_I2C_SDA_1") (class "Default")
      (node (ref "ADC_TEMP_1") (pin "18") (pinfunction "SDA_18") (pintype "bidirectional"))
      (node (ref "ADC_TEMP_2") (pin "18") (pinfunction "SDA_18") (pintype "bidirectional"))
      (node (ref "H2") (pin "18") (pinfunction "18_18") (pintype "bidirectional"))
      (node (ref "U$1") (pin "14") (pinfunction "C14_14") (pintype "bidirectional"))
      (node (ref "U$6") (pin "17") (pinfunction "SDA_17") (pintype "bidirectional"))
    )
    (net (code "79") (name "/Q6_RADIO_UART_RX") (class "Default")
      (node (ref "H1") (pin "18") (pinfunction "18_18") (pintype "bidirectional"))
    )
    (net (code "80") (name "/Q6_RADIO_UART_TX") (class "Default")
      (node (ref "H1") (pin "17") (pinfunction "17_17") (pintype "bidirectional"))
    )
    (net (code "81") (name "/Q6_SPI_CS0") (class "Default")
      (node (ref "H2") (pin "37") (pinfunction "37_37") (pintype "bidirectional"))
      (node (ref "U$1") (pin "20") (pinfunction "C20_20") (pintype "bidirectional"))
    )
    (net (code "82") (name "/Q6_SPI_CS1") (class "Default")
      (node (ref "H2") (pin "25") (pinfunction "25_25") (pintype "bidirectional"))
      (node (ref "U$1") (pin "21") (pinfunction "C21_21") (pintype "bidirectional"))
    )
    (net (code "83") (name "/Q6_SPI_SCLK") (class "Default")
      (node (ref "H2") (pin "21") (pinfunction "21_21") (pintype "bidirectional"))
      (node (ref "U$1") (pin "17") (pinfunction "C17_17") (pintype "bidirectional"))
    )
    (net (code "84") (name "/Q6_SPI_SDI_MISO") (class "Default")
      (node (ref "H2") (pin "35") (pinfunction "35_35") (pintype "bidirectional"))
      (node (ref "U$1") (pin "19") (pinfunction "C19_19") (pintype "bidirectional"))
    )
    (net (code "85") (name "/Q6_SPI_SDO_MOSI") (class "Default")
      (node (ref "H2") (pin "23") (pinfunction "23_23") (pintype "bidirectional"))
      (node (ref "U$1") (pin "18") (pinfunction "C18_18") (pintype "bidirectional"))
    )
    (net (code "86") (name "/SLR_PNL_GND") (class "Default")
      (node (ref "H1") (pin "30") (pinfunction "30_30") (pintype "bidirectional"))
    )
    (net (code "87") (name "/SOLAR_PANEL_1_3") (class "Default")
      (node (ref "H1") (pin "29") (pinfunction "29_29") (pintype "bidirectional"))
    )
    (net (code "88") (name "/SOLAR_PANEL_GND") (class "Default")
      (node (ref "H1") (pin "31") (pinfunction "31_31") (pintype "bidirectional"))
    )
    (net (code "89") (name "/THERMALGND1") (class "Default")
      (node (ref "ADC_TEMP_1") (pin "1") (pinfunction "AGND_1") (pintype "bidirectional"))
      (node (ref "ADC_TEMP_1") (pin "20") (pinfunction "AGND3_20") (pintype "bidirectional"))
      (node (ref "ADC_TEMP_1") (pin "3") (pinfunction "AGND1_3") (pintype "bidirectional"))
      (node (ref "ADC_TEMP_1") (pin "4") (pinfunction "AGND2_4") (pintype "bidirectional"))
      (node (ref "ADC_TEMP_2") (pin "1") (pinfunction "AGND_1") (pintype "bidirectional"))
      (node (ref "ADC_TEMP_2") (pin "20") (pinfunction "AGND3_20") (pintype "bidirectional"))
      (node (ref "ADC_TEMP_2") (pin "3") (pinfunction "AGND1_3") (pintype "bidirectional"))
      (node (ref "ADC_TEMP_2") (pin "4") (pinfunction "AGND2_4") (pintype "bidirectional"))
      (node (ref "H1") (pin "5") (pinfunction "5_5") (pintype "bidirectional"))
      (node (ref "R10") (pin "2") (pinfunction "2_2") (pintype "passive"))
      (node (ref "R9") (pin "1") (pinfunction "1_1") (pintype "passive"))
    )
    (net (code "90") (name "/TOP_TEMP_SOLAR_PANEL-1") (class "Default")
      (node (ref "ADC_TEMP_1") (pin "7") (pinfunction "VIN1_7") (pintype "bidirectional"))
      (node (ref "C8") (pin "2") (pinfunction "2_2") (pintype "passive"))
      (node (ref "H2") (pin "1") (pinfunction "1_1") (pintype "bidirectional"))
      (node (ref "R1") (pin "1") (pinfunction "1_1") (pintype "passive"))
    )
    (net (code "91") (name "/TOP_TEMP_SOLAR_PANEL-2") (class "Default")
      (node (ref "ADC_TEMP_1") (pin "14") (pinfunction "VIN2_14") (pintype "bidirectional"))
      (node (ref "C7") (pin "2") (pinfunction "2_2") (pintype "passive"))
      (node (ref "H2") (pin "3") (pinfunction "3_3") (pintype "bidirectional"))
      (node (ref "R2") (pin "1") (pinfunction "1_1") (pintype "passive"))
    )
    (net (code "92") (name "/TOP_TEMP_SOLAR_PANEL-3") (class "Default")
      (node (ref "ADC_TEMP_1") (pin "8") (pinfunction "VIN3_8") (pintype "bidirectional"))
      (node (ref "C6") (pin "2") (pinfunction "2_2") (pintype "passive"))
      (node (ref "H2") (pin "5") (pinfunction "5_5") (pintype "bidirectional"))
      (node (ref "R3") (pin "1") (pinfunction "1_1") (pintype "passive"))
    )
    (net (code "93") (name "/TOP_TEMP_SOLAR_PANEL-4") (class "Default")
      (node (ref "ADC_TEMP_1") (pin "13") (pinfunction "VIN4_13") (pintype "bidirectional"))
      (node (ref "C5") (pin "2") (pinfunction "2_2") (pintype "passive"))
      (node (ref "H2") (pin "7") (pinfunction "7_7") (pintype "bidirectional"))
      (node (ref "R4") (pin "1") (pinfunction "1_1") (pintype "passive"))
    )
    (net (code "94") (name "/~{MANUAL_RESET}") (class "Default")
      (node (ref "U$4") (pin "3") (pinfunction "~{MR}_3") (pintype "bidirectional"))
    )
    (net (code "95") (name "/~{PA3_JAG_TRST}") (class "Default")
      (node (ref "U$1") (pin "34") (pinfunction "C34_34") (pintype "bidirectional"))
    )
    (net (code "96") (name "/~{WAKE_UP}") (class "Default")
      (node (ref "U$1") (pin "46") (pinfunction "C46_46") (pintype "bidirectional"))
    )
    (net (code "97") (name "GND") (class "Default")
      (node (ref "ADC_TEMP_1") (pin "15") (pinfunction "AS_15") (pintype "bidirectional"))
      (node (ref "C1") (pin "1") (pinfunction "1_1") (pintype "passive"))
      (node (ref "C10") (pin "2") (pinfunction "2_2") (pintype "passive"))
      (node (ref "C11") (pin "2") (pinfunction "2_2") (pintype "passive"))
      (node (ref "C12") (pin "1") (pinfunction "1_1") (pintype "passive"))
      (node (ref "C13") (pin "1") (pinfunction "1_1") (pintype "passive"))
      (node (ref "C14") (pin "2") (pinfunction "2_2") (pintype "passive"))
      (node (ref "C15") (pin "2") (pinfunction "2_2") (pintype "passive"))
      (node (ref "C16") (pin "1") (pinfunction "1_1") (pintype "passive"))
      (node (ref "C17") (pin "2") (pinfunction "2_2") (pintype "passive"))
      (node (ref "C18") (pin "1") (pinfunction "1_1") (pintype "passive"))
      (node (ref "C19") (pin "1") (pinfunction "1_1") (pintype "passive"))
      (node (ref "C2") (pin "1") (pinfunction "1_1") (pintype "passive"))
      (node (ref "C3") (pin "1") (pinfunction "1_1") (pintype "passive"))
      (node (ref "C4") (pin "1") (pinfunction "1_1") (pintype "passive"))
      (node (ref "C5") (pin "1") (pinfunction "1_1") (pintype "passive"))
      (node (ref "C6") (pin "1") (pinfunction "1_1") (pintype "passive"))
      (node (ref "C7") (pin "1") (pinfunction "1_1") (pintype "passive"))
      (node (ref "C8") (pin "1") (pinfunction "1_1") (pintype "passive"))
      (node (ref "C9") (pin "2") (pinfunction "2_2") (pintype "passive"))
      (node (ref "D1") (pin "A") (pinfunction "A_A") (pintype "passive"))
      (node (ref "H1") (pin "15") (pinfunction "15_15") (pintype "bidirectional"))
      (node (ref "H1") (pin "19") (pinfunction "19_19") (pintype "bidirectional"))
      (node (ref "H1") (pin "23") (pinfunction "23_23") (pintype "bidirectional"))
      (node (ref "H1") (pin "27") (pinfunction "27_27") (pintype "bidirectional"))
      (node (ref "H1") (pin "34") (pinfunction "34_34") (pintype "bidirectional"))
      (node (ref "H1") (pin "37") (pinfunction "37_37") (pintype "bidirectional"))
      (node (ref "H1") (pin "41") (pinfunction "41_41") (pintype "bidirectional"))
      (node (ref "H1") (pin "44") (pinfunction "44_44") (pintype "bidirectional"))
      (node (ref "H1") (pin "45") (pinfunction "45_45") (pintype "bidirectional"))
      (node (ref "H1") (pin "48") (pinfunction "48_48") (pintype "bidirectional"))
      (node (ref "H1") (pin "49") (pinfunction "49_49") (pintype "bidirectional"))
      (node (ref "H1") (pin "52") (pinfunction "52_52") (pintype "bidirectional"))
      (node (ref "H2") (pin "16") (pinfunction "16_16") (pintype "bidirectional"))
      (node (ref "H2") (pin "17") (pinfunction "17_17") (pintype "bidirectional"))
      (node (ref "H2") (pin "19") (pinfunction "19_19") (pintype "bidirectional"))
      (node (ref "H2") (pin "22") (pinfunction "22_22") (pintype "bidirectional"))
      (node (ref "H2") (pin "26") (pinfunction "26_26") (pintype "bidirectional"))
      (node (ref "H2") (pin "4") (pinfunction "4_4") (pintype "bidirectional"))
      (node (ref "R11") (pin "2") (pinfunction "2_2") (pintype "passive"))
      (node (ref "R9") (pin "2") (pinfunction "2_2") (pintype "passive"))
      (node (ref "U$1") (pin "1") (pinfunction "C1_1") (pintype "bidirectional"))
      (node (ref "U$1") (pin "10") (pinfunction "C10_10") (pintype "bidirectional"))
      (node (ref "U$1") (pin "2") (pinfunction "C2_2") (pintype "bidirectional"))
      (node (ref "U$1") (pin "27") (pinfunction "C27_27") (pintype "bidirectional"))
      (node (ref "U$1") (pin "28") (pinfunction "C28_28") (pintype "bidirectional"))
      (node (ref "U$1") (pin "39") (pinfunction "C39_39") (pintype "bidirectional"))
      (node (ref "U$1") (pin "40") (pinfunction "C40_40") (pintype "bidirectional"))
      (node (ref "U$1") (pin "47") (pinfunction "C47_47") (pintype "bidirectional"))
      (node (ref "U$1") (pin "48") (pinfunction "C48_48") (pintype "bidirectional"))
      (node (ref "U$1") (pin "7") (pinfunction "C7_7") (pintype "bidirectional"))
      (node (ref "U$1") (pin "8") (pinfunction "C8_8") (pintype "bidirectional"))
      (node (ref "U$1") (pin "9") (pinfunction "C9_9") (pintype "bidirectional"))
      (node (ref "U$4") (pin "2") (pinfunction "GND_2") (pintype "bidirectional"))
      (node (ref "U$5") (pin "-") (pinfunction "-_-") (pintype "passive"))
      (node (ref "U$6") (pin "1") (pinfunction "N.C.1_1") (pintype "bidirectional"))
      (node (ref "U$6") (pin "10") (pinfunction "N.C.6_10") (pintype "bidirectional"))
      (node (ref "U$6") (pin "11") (pinfunction "N.C.7_11") (pintype "bidirectional"))
      (node (ref "U$6") (pin "12") (pinfunction "N.C.8_12") (pintype "bidirectional"))
      (node (ref "U$6") (pin "13") (pinfunction "N.C.9_13") (pintype "bidirectional"))
      (node (ref "U$6") (pin "14") (pinfunction "N.C.10_14") (pintype "bidirectional"))
      (node (ref "U$6") (pin "15") (pinfunction "GND_15") (pintype "bidirectional"))
      (node (ref "U$6") (pin "19") (pinfunction "N.C.11_19") (pintype "bidirectional"))
      (node (ref "U$6") (pin "2") (pinfunction "N.C.2_2") (pintype "bidirectional"))
      (node (ref "U$6") (pin "7") (pinfunction "N.C.3_7") (pintype "bidirectional"))
      (node (ref "U$6") (pin "8") (pinfunction "N.C.4_8") (pintype "bidirectional"))
      (node (ref "U$6") (pin "9") (pinfunction "N.C.5_9") (pintype "bidirectional"))
    )
    (net (code "98") (name "Net-(ADC_TEMP_1-REF_IN)") (class "Default")
      (node (ref "ADC_TEMP_1") (pin "6") (pinfunction "REF_IN_6") (pintype "bidirectional"))
      (node (ref "ADC_TEMP_2") (pin "6") (pinfunction "REF_IN_6") (pintype "bidirectional"))
      (node (ref "C19") (pin "2") (pinfunction "2_2") (pintype "passive"))
      (node (ref "D1") (pin "C") (pinfunction "C_C") (pintype "passive"))
      (node (ref "R17") (pin "1") (pinfunction "1_1") (pintype "passive"))
    )
    (net (code "99") (name "Net-(ADC_TEMP_2-AS)") (class "Default")
      (node (ref "ADC_TEMP_2") (pin "15") (pinfunction "AS_15") (pintype "bidirectional"))
      (node (ref "R16") (pin "2") (pinfunction "2_2") (pintype "passive"))
    )
    (net (code "100") (name "Net-(ADC_TEMP_2-VIN4)") (class "Default")
      (node (ref "ADC_TEMP_2") (pin "13") (pinfunction "VIN4_13") (pintype "bidirectional"))
      (node (ref "C16") (pin "2") (pinfunction "2_2") (pintype "passive"))
      (node (ref "R13") (pin "1") (pinfunction "1_1") (pintype "passive"))
    )
    (net (code "101") (name "Net-(U$5-+)") (class "Default")
      (node (ref "U$5") (pin "+$1") (pinfunction "+_+$1") (pintype "passive"))
      (node (ref "U$5") (pin "+$2") (pinfunction "+1_+$2") (pintype "passive"))
      (node (ref "U$6") (pin "16") (pinfunction "VBAT_16") (pintype "bidirectional"))
    )
    (net (code "102") (name "unconnected-(ADC_TEMP_1-ALERT{slash}BUSY-Pad17)") (class "Default")
      (node (ref "ADC_TEMP_1") (pin "17") (pinfunction "ALERT/BUSY_17") (pintype "bidirectional"))
    )
    (net (code "103") (name "unconnected-(ADC_TEMP_2-ALERT{slash}BUSY-Pad17)") (class "Default")
      (node (ref "ADC_TEMP_2") (pin "17") (pinfunction "ALERT/BUSY_17") (pintype "bidirectional"))
    )
    (net (code "104") (name "unconnected-(ADC_TEMP_2-VIN1-Pad7)") (class "Default")
      (node (ref "ADC_TEMP_2") (pin "7") (pinfunction "VIN1_7") (pintype "bidirectional"))
    )
    (net (code "105") (name "unconnected-(ADC_TEMP_2-VIN2-Pad14)") (class "Default")
      (node (ref "ADC_TEMP_2") (pin "14") (pinfunction "VIN2_14") (pintype "bidirectional"))
    )
    (net (code "106") (name "unconnected-(ADC_TEMP_2-VIN5-Pad9)") (class "Default")
      (node (ref "ADC_TEMP_2") (pin "9") (pinfunction "VIN5_9") (pintype "bidirectional"))
    )
    (net (code "107") (name "unconnected-(ADC_TEMP_2-VIN6-Pad12)") (class "Default")
      (node (ref "ADC_TEMP_2") (pin "12") (pinfunction "VIN6_12") (pintype "bidirectional"))
    )
    (net (code "108") (name "unconnected-(H1-Pad2)") (class "Default")
      (node (ref "H1") (pin "2") (pinfunction "2_2") (pintype "bidirectional"))
    )
    (net (code "109") (name "unconnected-(U$2-PadX1)") (class "Default")
      (node (ref "U$2") (pin "X1") (pinfunction "X1_X1") (pintype "bidirectional"))
    )
    (net (code "110") (name "unconnected-(U$2-PadX2)") (class "Default")
      (node (ref "U$2") (pin "X2") (pinfunction "X2_X2") (pintype "bidirectional"))
    )
    (net (code "111") (name "unconnected-(U$6-32KHZ-Pad3)") (class "Default")
      (node (ref "U$6") (pin "3") (pinfunction "32KHZ_3") (pintype "bidirectional"))
    )
    (net (code "112") (name "unconnected-(U$6-SCL2-Pad20)") (class "Default")
      (node (ref "U$6") (pin "20") (pinfunction "SCL2_20") (pintype "bidirectional"))
    )
  )
)
